# Microcontroller.net
KiCad netlist of a schematic drawn in Altium Designer
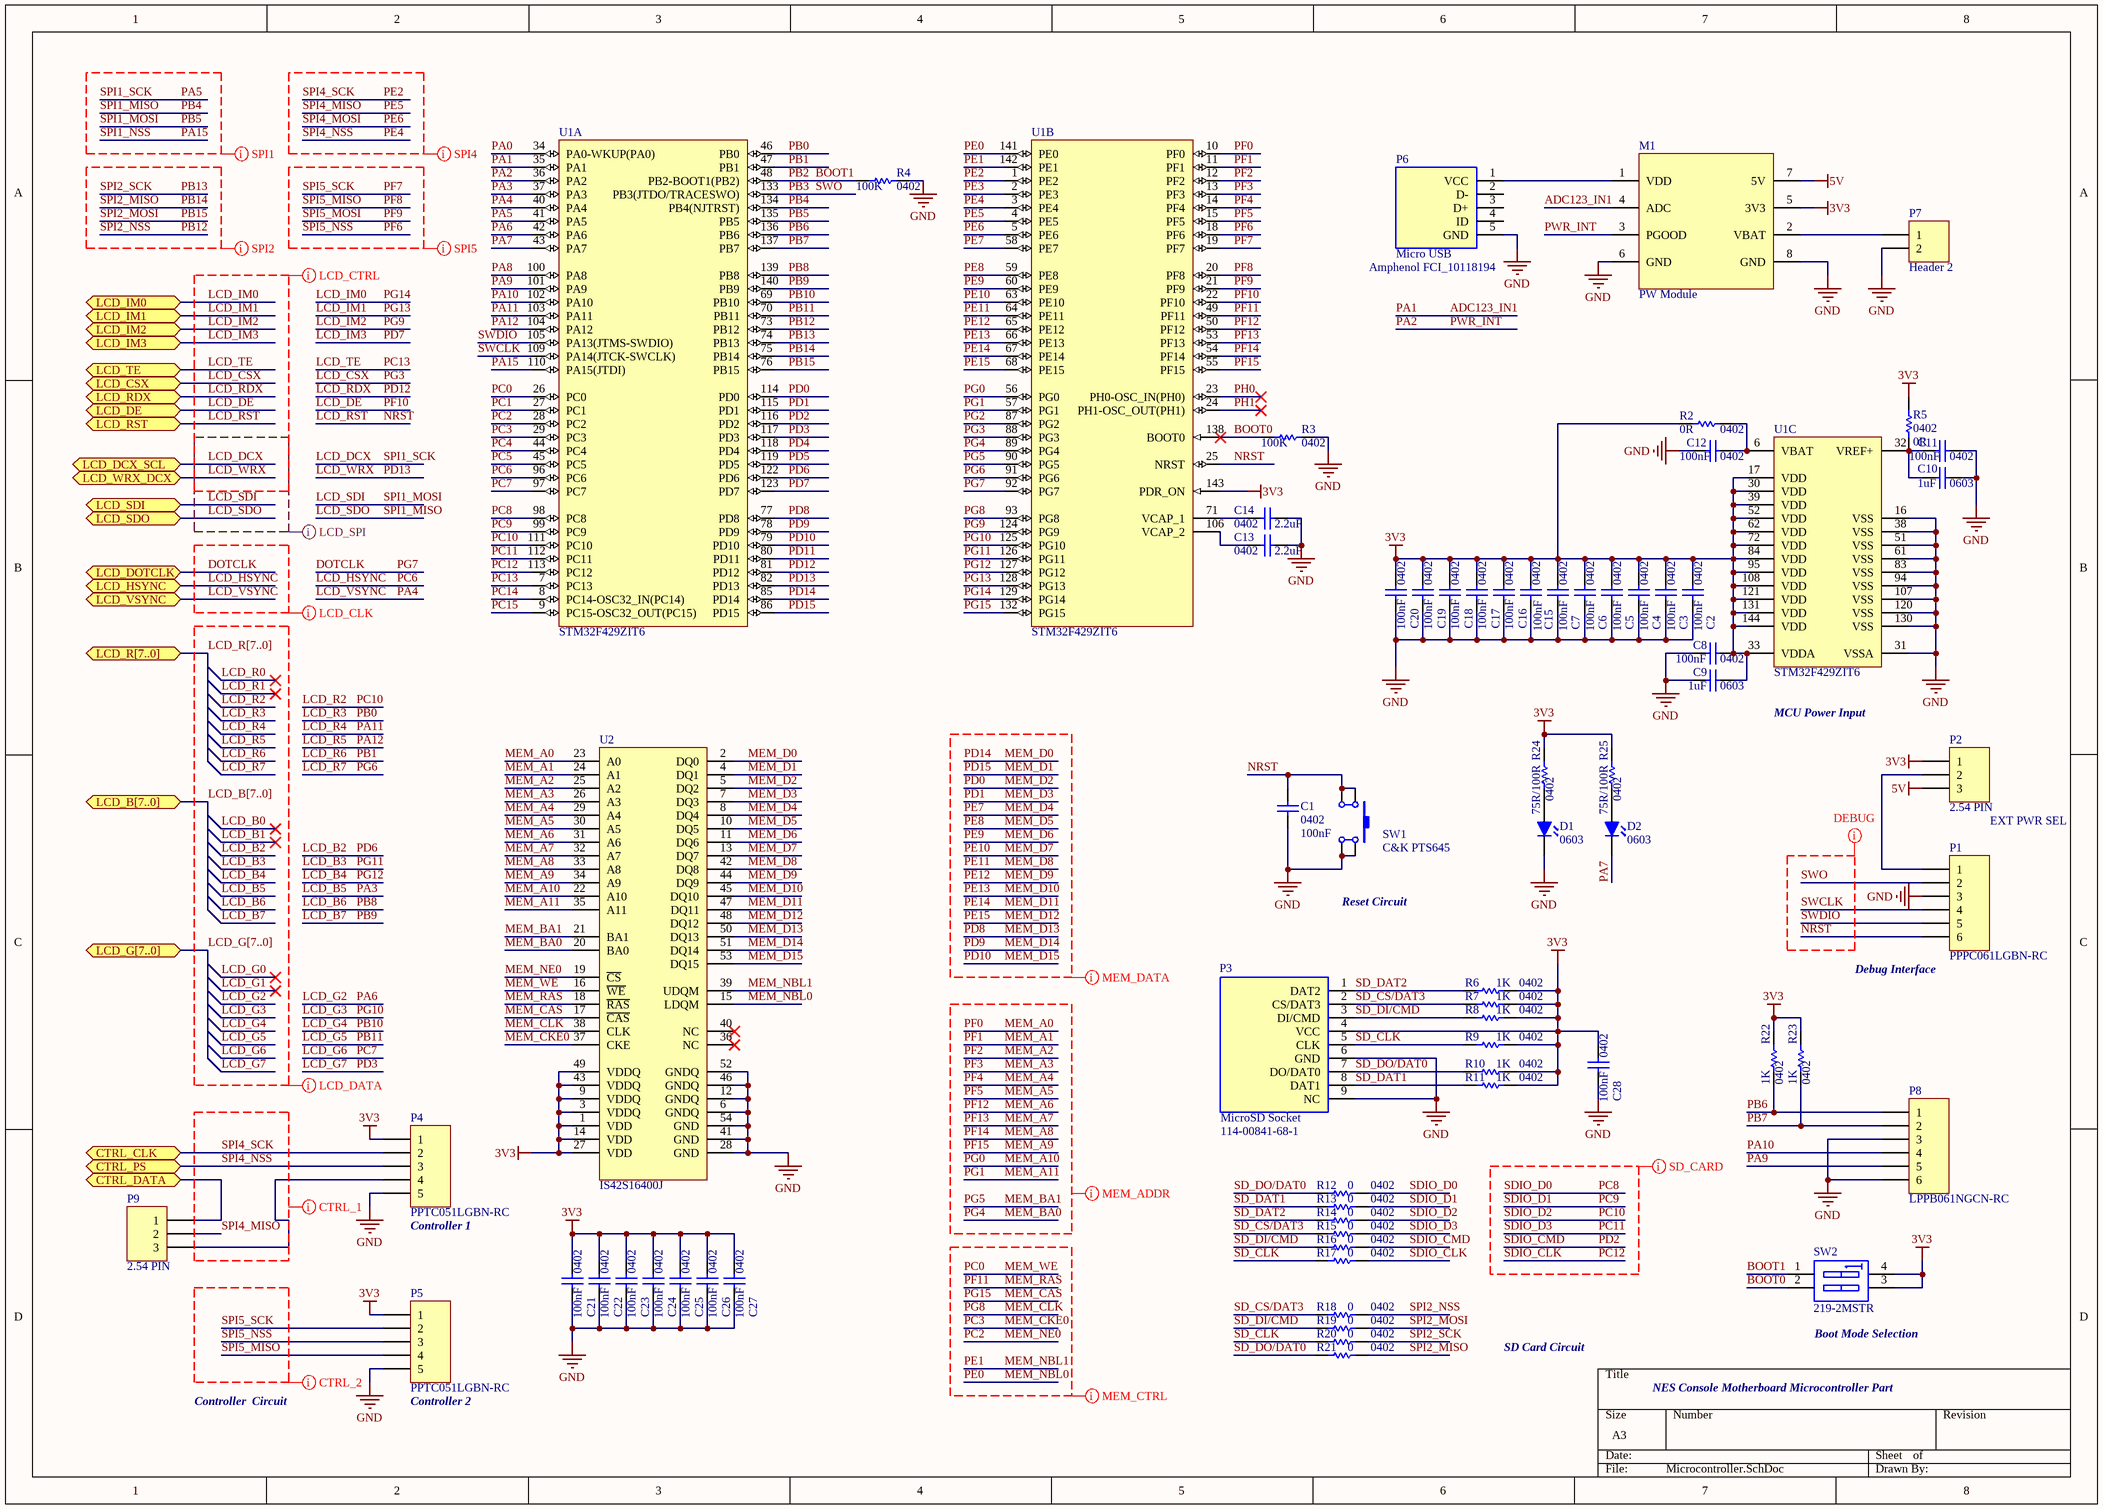
[diagram p0: Microcontroller.SchDoc]

(export (version "E")
  (design (tool "Eeschema 10.0.6"))
  (components
    (comp (ref "C1")
      (value "0402")
      (footprint "CAPC1005X07N")
      (description "Capacitor")
      (fields (field (name "ALTIUM_VALUE") "100nF") (field (name "PUBLISHER") "Altium Limited"))
      (libsource (lib "Miscellaneous Devices") (part "Cap"))
    )
    (comp (ref "C2")
      (value "0402")
      (footprint "CAPC1005X07N")
      (description "Capacitor")
      (fields (field (name "ALTIUM_VALUE") "100nF") (field (name "PUBLISHER") "Altium Limited"))
      (libsource (lib "Miscellaneous Devices") (part "Cap"))
    )
    (comp (ref "C3")
      (value "0402")
      (footprint "CAPC1005X07N")
      (description "Capacitor")
      (fields (field (name "ALTIUM_VALUE") "100nF") (field (name "PUBLISHER") "Altium Limited"))
      (libsource (lib "Miscellaneous Devices") (part "Cap"))
    )
    (comp (ref "C4")
      (value "0402")
      (footprint "CAPC1005X07N")
      (description "Capacitor")
      (fields (field (name "ALTIUM_VALUE") "100nF") (field (name "PUBLISHER") "Altium Limited"))
      (libsource (lib "Miscellaneous Devices") (part "Cap"))
    )
    (comp (ref "C5")
      (value "0402")
      (footprint "CAPC1005X07N")
      (description "Capacitor")
      (fields (field (name "ALTIUM_VALUE") "100nF") (field (name "PUBLISHER") "Altium Limited"))
      (libsource (lib "Miscellaneous Devices") (part "Cap"))
    )
    (comp (ref "C6")
      (value "0402")
      (footprint "CAPC1005X07N")
      (description "Capacitor")
      (fields (field (name "ALTIUM_VALUE") "100nF") (field (name "PUBLISHER") "Altium Limited"))
      (libsource (lib "Miscellaneous Devices") (part "Cap"))
    )
    (comp (ref "C7")
      (value "0402")
      (footprint "CAPC1005X07N")
      (description "Capacitor")
      (fields (field (name "ALTIUM_VALUE") "100nF") (field (name "PUBLISHER") "Altium Limited"))
      (libsource (lib "Miscellaneous Devices") (part "Cap"))
    )
    (comp (ref "C8")
      (value "0402")
      (footprint "CAPC1005X07N")
      (description "Capacitor")
      (fields (field (name "ALTIUM_VALUE") "100nF") (field (name "PUBLISHER") "Altium Limited"))
      (libsource (lib "Miscellaneous Devices") (part "Cap"))
    )
    (comp (ref "C9")
      (value "0603")
      (footprint "CAPC1608X10N")
      (description "Capacitor")
      (fields (field (name "ALTIUM_VALUE") "1uF") (field (name "PUBLISHER") "Altium Limited"))
      (libsource (lib "Miscellaneous Devices") (part "Cap"))
    )
    (comp (ref "C10")
      (value "0603")
      (footprint "CAPC1608X10N")
      (description "Capacitor")
      (fields (field (name "ALTIUM_VALUE") "1uF") (field (name "PUBLISHER") "Altium Limited"))
      (libsource (lib "Miscellaneous Devices") (part "Cap"))
    )
    (comp (ref "C11")
      (value "0402")
      (footprint "CAPC1005X07N")
      (description "Capacitor")
      (fields (field (name "ALTIUM_VALUE") "100nF") (field (name "PUBLISHER") "Altium Limited"))
      (libsource (lib "Miscellaneous Devices") (part "Cap"))
    )
    (comp (ref "C12")
      (value "0402")
      (footprint "CAPC1005X07N")
      (description "Capacitor")
      (fields (field (name "ALTIUM_VALUE") "100nF") (field (name "PUBLISHER") "Altium Limited"))
      (libsource (lib "Miscellaneous Devices") (part "Cap"))
    )
    (comp (ref "C13")
      (value "0402")
      (footprint "CAPC1005X07N")
      (description "Capacitor")
      (fields (field (name "ALTIUM_VALUE") "2.2uF") (field (name "PUBLISHER") "Altium Limited"))
      (libsource (lib "Miscellaneous Devices") (part "Cap"))
    )
    (comp (ref "C14")
      (value "0402")
      (footprint "CAPC1005X07N")
      (description "Capacitor")
      (fields (field (name "ALTIUM_VALUE") "2.2uF") (field (name "PUBLISHER") "Altium Limited"))
      (libsource (lib "Miscellaneous Devices") (part "Cap"))
    )
    (comp (ref "C15")
      (value "0402")
      (footprint "CAPC1005X07N")
      (description "Capacitor")
      (fields (field (name "ALTIUM_VALUE") "100nF") (field (name "PUBLISHER") "Altium Limited"))
      (libsource (lib "Miscellaneous Devices") (part "Cap"))
    )
    (comp (ref "C16")
      (value "0402")
      (footprint "CAPC1005X07N")
      (description "Capacitor")
      (fields (field (name "ALTIUM_VALUE") "100nF") (field (name "PUBLISHER") "Altium Limited"))
      (libsource (lib "Miscellaneous Devices") (part "Cap"))
    )
    (comp (ref "C17")
      (value "0402")
      (footprint "CAPC1005X07N")
      (description "Capacitor")
      (fields (field (name "ALTIUM_VALUE") "100nF") (field (name "PUBLISHER") "Altium Limited"))
      (libsource (lib "Miscellaneous Devices") (part "Cap"))
    )
    (comp (ref "C18")
      (value "0402")
      (footprint "CAPC1005X07N")
      (description "Capacitor")
      (fields (field (name "ALTIUM_VALUE") "100nF") (field (name "PUBLISHER") "Altium Limited"))
      (libsource (lib "Miscellaneous Devices") (part "Cap"))
    )
    (comp (ref "C19")
      (value "0402")
      (footprint "CAPC1005X07N")
      (description "Capacitor")
      (fields (field (name "ALTIUM_VALUE") "100nF") (field (name "PUBLISHER") "Altium Limited"))
      (libsource (lib "Miscellaneous Devices") (part "Cap"))
    )
    (comp (ref "C20")
      (value "0402")
      (footprint "CAPC1005X07N")
      (description "Capacitor")
      (fields (field (name "ALTIUM_VALUE") "100nF") (field (name "PUBLISHER") "Altium Limited"))
      (libsource (lib "Miscellaneous Devices") (part "Cap"))
    )
    (comp (ref "C21")
      (value "0402")
      (footprint "CAPC1005X07N")
      (description "Capacitor")
      (fields (field (name "ALTIUM_VALUE") "100nF") (field (name "PUBLISHER") "Altium Limited"))
      (libsource (lib "Miscellaneous Devices") (part "Cap"))
    )
    (comp (ref "C22")
      (value "0402")
      (footprint "CAPC1005X07N")
      (description "Capacitor")
      (fields (field (name "ALTIUM_VALUE") "100nF") (field (name "PUBLISHER") "Altium Limited"))
      (libsource (lib "Miscellaneous Devices") (part "Cap"))
    )
    (comp (ref "C23")
      (value "0402")
      (footprint "CAPC1005X07N")
      (description "Capacitor")
      (fields (field (name "ALTIUM_VALUE") "100nF") (field (name "PUBLISHER") "Altium Limited"))
      (libsource (lib "Miscellaneous Devices") (part "Cap"))
    )
    (comp (ref "C24")
      (value "0402")
      (footprint "CAPC1005X07N")
      (description "Capacitor")
      (fields (field (name "ALTIUM_VALUE") "100nF") (field (name "PUBLISHER") "Altium Limited"))
      (libsource (lib "Miscellaneous Devices") (part "Cap"))
    )
    (comp (ref "C25")
      (value "0402")
      (footprint "CAPC1005X07N")
      (description "Capacitor")
      (fields (field (name "ALTIUM_VALUE") "100nF") (field (name "PUBLISHER") "Altium Limited"))
      (libsource (lib "Miscellaneous Devices") (part "Cap"))
    )
    (comp (ref "C26")
      (value "0402")
      (footprint "CAPC1005X07N")
      (description "Capacitor")
      (fields (field (name "ALTIUM_VALUE") "100nF") (field (name "PUBLISHER") "Altium Limited"))
      (libsource (lib "Miscellaneous Devices") (part "Cap"))
    )
    (comp (ref "C27")
      (value "0402")
      (footprint "CAPC1005X07N")
      (description "Capacitor")
      (fields (field (name "ALTIUM_VALUE") "100nF") (field (name "PUBLISHER") "Altium Limited"))
      (libsource (lib "Miscellaneous Devices") (part "Cap"))
    )
    (comp (ref "C28")
      (value "0402")
      (footprint "CAPC1005X07N")
      (description "Capacitor")
      (fields (field (name "ALTIUM_VALUE") "100nF") (field (name "PUBLISHER") "Altium Limited"))
      (libsource (lib "Miscellaneous Devices") (part "Cap"))
    )
    (comp (ref "D1")
      (value "0603")
      (footprint "RESC1608X06N")
      (description "General LED")
      (libsource (lib "Schematic_Diode") (part "LED-1"))
    )
    (comp (ref "D2")
      (value "0603")
      (footprint "RESC1608X06N")
      (description "General LED")
      (libsource (lib "Schematic_Diode") (part "LED-1"))
    )
    (comp (ref "M1")
      (value "PW Module")
      (footprint "Power Module")
      (description "Power Supply Module")
      (libsource (lib "Schematic_Modules_NES") (part "PW Module"))
    )
    (comp (ref "P1")
      (value "PPPC061LGBN-RC")
      (footprint "HDR1X6_RANG")
      (description "Header, 6-Pin")
      (fields (field (name "PUBLISHER") "Altium Limited"))
      (libsource (lib "Miscellaneous Connectors") (part "Header 6"))
    )
    (comp (ref "P2")
      (value "2.54 PIN")
      (footprint "HDR1X3")
      (description "Header, 3-Pin")
      (fields (field (name "PUBLISHER") "Altium Limited"))
      (libsource (lib "Miscellaneous Connectors") (part "Header 3"))
    )
    (comp (ref "P3")
      (value "114-00841-68-1")
      (footprint "Amphenol_114-00841-68")
      (description "CONN MICRO SD CARD PUSH-PULL R/A")
      (fields
        (field (name "MANUFACTURER") "Amphenol Commercial")
        (field (name "MANUFACTURER PART NUMBER") "114-00841-68")
        (field (name "CONNECTOR TYPE") "MicroSD Socket")
      )
      (libsource (lib "Schematic_Connectors_USB") (part "Amphenol 114-00841-68-1"))
    )
    (comp (ref "P4")
      (value "PPTC051LGBN-RC")
      (footprint "HDR1X5_RANG")
      (description "Header, 5-Pin")
      (fields (field (name "PUBLISHER") "Altium Limited"))
      (libsource (lib "Miscellaneous Connectors") (part "Header 5"))
    )
    (comp (ref "P5")
      (value "PPTC051LGBN-RC")
      (footprint "HDR1X5_RANG")
      (description "Header, 5-Pin")
      (fields (field (name "PUBLISHER") "Altium Limited"))
      (libsource (lib "Miscellaneous Connectors") (part "Header 5"))
    )
    (comp (ref "P6")
      (value "Amphenol FCI_10118194")
      (footprint "USB_Mirco_Amphenol FCI_10118194")
      (description "General  Micro USB")
      (fields (field (name "CONNECTOR TYPE") "Micro USB"))
      (libsource (lib "Schematic_Connectors_USB") (part "CONN_MICRO_USB"))
    )
    (comp (ref "P7")
      (value "Header 2")
      (footprint "HDR1X2")
      (description "Header, 2-Pin")
      (fields (field (name "PUBLISHER") "Altium Limited"))
      (libsource (lib "Miscellaneous Connectors") (part "Header 2"))
    )
    (comp (ref "P8")
      (value "LPPB061NGCN-RC")
      (footprint "MHDR1X6_RANG")
      (description "Header, 6-Pin")
      (fields (field (name "PUBLISHER") "Altium Limited"))
      (libsource (lib "Miscellaneous Connectors") (part "Header 6"))
    )
    (comp (ref "P9")
      (value "2.54 PIN")
      (footprint "HDR1X3")
      (description "Header, 3-Pin")
      (fields (field (name "PUBLISHER") "Altium Limited"))
      (libsource (lib "") (part "Header 3_1"))
    )
    (comp (ref "R2")
      (value "0402")
      (footprint "RESC1005X04N")
      (description "Resistor")
      (fields (field (name "ALTIUM_VALUE") "0R") (field (name "PUBLISHER") "Altium Limited"))
      (libsource (lib "Miscellaneous Devices") (part "Res1"))
    )
    (comp (ref "R3")
      (value "0402")
      (footprint "RESC1005X04N")
      (description "Resistor")
      (fields (field (name "ALTIUM_VALUE") "100K") (field (name "PUBLISHER") "Altium Limited"))
      (libsource (lib "Miscellaneous Devices") (part "Res1"))
    )
    (comp (ref "R4")
      (value "0402")
      (footprint "RESC1005X04N")
      (description "Resistor")
      (fields (field (name "ALTIUM_VALUE") "100K") (field (name "PUBLISHER") "Altium Limited"))
      (libsource (lib "Miscellaneous Devices") (part "Res1"))
    )
    (comp (ref "R5")
      (value "0402")
      (footprint "RESC1005X04N")
      (description "Resistor")
      (fields (field (name "ALTIUM_VALUE") "0R") (field (name "PUBLISHER") "Altium Limited"))
      (libsource (lib "Miscellaneous Devices") (part "Res1"))
    )
    (comp (ref "R6")
      (value "0402")
      (footprint "RESC1005X04N")
      (description "Resistor")
      (fields (field (name "ALTIUM_VALUE") "1K") (field (name "PUBLISHER") "Altium Limited"))
      (libsource (lib "Miscellaneous Devices") (part "Res1"))
    )
    (comp (ref "R7")
      (value "0402")
      (footprint "RESC1005X04N")
      (description "Resistor")
      (fields (field (name "ALTIUM_VALUE") "1K") (field (name "PUBLISHER") "Altium Limited"))
      (libsource (lib "Miscellaneous Devices") (part "Res1"))
    )
    (comp (ref "R8")
      (value "0402")
      (footprint "RESC1005X04N")
      (description "Resistor")
      (fields (field (name "ALTIUM_VALUE") "1K") (field (name "PUBLISHER") "Altium Limited"))
      (libsource (lib "Miscellaneous Devices") (part "Res1"))
    )
    (comp (ref "R9")
      (value "0402")
      (footprint "RESC1005X04N")
      (description "Resistor")
      (fields (field (name "ALTIUM_VALUE") "1K") (field (name "PUBLISHER") "Altium Limited"))
      (libsource (lib "Miscellaneous Devices") (part "Res1"))
    )
    (comp (ref "R10")
      (value "0402")
      (footprint "RESC1005X04N")
      (description "Resistor")
      (fields (field (name "ALTIUM_VALUE") "1K") (field (name "PUBLISHER") "Altium Limited"))
      (libsource (lib "Miscellaneous Devices") (part "Res1"))
    )
    (comp (ref "R11")
      (value "0402")
      (footprint "RESC1005X04N")
      (description "Resistor")
      (fields (field (name "ALTIUM_VALUE") "1K") (field (name "PUBLISHER") "Altium Limited"))
      (libsource (lib "Miscellaneous Devices") (part "Res1"))
    )
    (comp (ref "R12")
      (value "0402")
      (footprint "RESC1005X04N")
      (description "Resistor")
      (fields (field (name "ALTIUM_VALUE") "0") (field (name "PUBLISHER") "Altium Limited"))
      (libsource (lib "Miscellaneous Devices") (part "Res1"))
    )
    (comp (ref "R13")
      (value "0402")
      (footprint "RESC1005X04N")
      (description "Resistor")
      (fields (field (name "ALTIUM_VALUE") "0") (field (name "PUBLISHER") "Altium Limited"))
      (libsource (lib "Miscellaneous Devices") (part "Res1"))
    )
    (comp (ref "R14")
      (value "0402")
      (footprint "RESC1005X04N")
      (description "Resistor")
      (fields (field (name "ALTIUM_VALUE") "0") (field (name "PUBLISHER") "Altium Limited"))
      (libsource (lib "Miscellaneous Devices") (part "Res1"))
    )
    (comp (ref "R15")
      (value "0402")
      (footprint "RESC1005X04N")
      (description "Resistor")
      (fields (field (name "ALTIUM_VALUE") "0") (field (name "PUBLISHER") "Altium Limited"))
      (libsource (lib "Miscellaneous Devices") (part "Res1"))
    )
    (comp (ref "R16")
      (value "0402")
      (footprint "RESC1005X04N")
      (description "Resistor")
      (fields (field (name "ALTIUM_VALUE") "0") (field (name "PUBLISHER") "Altium Limited"))
      (libsource (lib "Miscellaneous Devices") (part "Res1"))
    )
    (comp (ref "R17")
      (value "0402")
      (footprint "RESC1005X04N")
      (description "Resistor")
      (fields (field (name "ALTIUM_VALUE") "0") (field (name "PUBLISHER") "Altium Limited"))
      (libsource (lib "Miscellaneous Devices") (part "Res1"))
    )
    (comp (ref "R18")
      (value "0402")
      (footprint "RESC1005X04N")
      (description "Resistor")
      (fields (field (name "ALTIUM_VALUE") "0") (field (name "PUBLISHER") "Altium Limited"))
      (libsource (lib "Miscellaneous Devices") (part "Res1"))
    )
    (comp (ref "R19")
      (value "0402")
      (footprint "RESC1005X04N")
      (description "Resistor")
      (fields (field (name "ALTIUM_VALUE") "0") (field (name "PUBLISHER") "Altium Limited"))
      (libsource (lib "Miscellaneous Devices") (part "Res1"))
    )
    (comp (ref "R20")
      (value "0402")
      (footprint "RESC1005X04N")
      (description "Resistor")
      (fields (field (name "ALTIUM_VALUE") "0") (field (name "PUBLISHER") "Altium Limited"))
      (libsource (lib "Miscellaneous Devices") (part "Res1"))
    )
    (comp (ref "R21")
      (value "0402")
      (footprint "RESC1005X04N")
      (description "Resistor")
      (fields (field (name "ALTIUM_VALUE") "0") (field (name "PUBLISHER") "Altium Limited"))
      (libsource (lib "Miscellaneous Devices") (part "Res1"))
    )
    (comp (ref "R22")
      (value "0402")
      (footprint "RESC1005X04N")
      (description "Resistor")
      (fields (field (name "ALTIUM_VALUE") "1K") (field (name "PUBLISHER") "Altium Limited"))
      (libsource (lib "Miscellaneous Devices") (part "Res1"))
    )
    (comp (ref "R23")
      (value "0402")
      (footprint "RESC1005X04N")
      (description "Resistor")
      (fields (field (name "ALTIUM_VALUE") "1K") (field (name "PUBLISHER") "Altium Limited"))
      (libsource (lib "Miscellaneous Devices") (part "Res1"))
    )
    (comp (ref "R24")
      (value "0402")
      (footprint "RESC1005X04N")
      (description "Resistor")
      (fields (field (name "ALTIUM_VALUE") "75R/100R") (field (name "PUBLISHER") "Altium Limited"))
      (libsource (lib "Miscellaneous Devices") (part "Res1"))
    )
    (comp (ref "R25")
      (value "0402")
      (footprint "RESC1005X04N")
      (description "Resistor")
      (fields (field (name "ALTIUM_VALUE") "75R/100R") (field (name "PUBLISHER") "Altium Limited"))
      (libsource (lib "Miscellaneous Devices") (part "Res1"))
    )
    (comp (ref "SW1")
      (value "C&K PTS645")
      (footprint "C&K_PTS645_SMT")
      (description "General Tactile Switch")
      (libsource (lib "Schematic_Switches") (part "SW_TACT"))
    )
    (comp (ref "SW2")
      (value "219-2MSTR")
      (footprint "CTS_219-2_SMT")
      (description "DIP Switch, 2 Position, SPST")
      (fields (field (name "PUBLISHER") "Altium Limited"))
      (libsource (lib "Schematic_Switches") (part "SW_DIP-2"))
    )
    (comp (ref "U1")
      (value "STM32F429ZIT6")
      (footprint "STM-LQFP144_N")
      (fields (field (name "MANUFACTURER") "STMicroelectronics"))
      (libsource (lib "STMicroelectronics STM32 F4") (part "STM32F429ZIT6"))
    )
    (comp (ref "U2")
      (value "IS42S16400J")
      (footprint "TSOP80P1180X120-54N")
      (description "DRAM 64M (4Mx16) 166MHz SDR SDRAM, 3.3V")
      (fields
        (field (name "MANUFACTURER") "ISSI")
        (field (name "MANUFACTURER PART NUMBER") "IS42S16400J-6TLI")
      )
      (libsource (lib "Schematic_Memory") (part "IS42S16400J"))
    )
  )
  (nets
    (net (code "1") (name "/ADC123_IN1") (class "Default")
      (node (ref "M1") (pin "4") (pinfunction "ADC_4") (pintype "passive"))
      (node (ref "U1") (pin "35") (pinfunction "PA1_35") (pintype "bidirectional"))
    )
    (net (code "2") (name "/BOOT0") (class "Default")
      (node (ref "R3") (pin "2") (pinfunction "2_2") (pintype "passive"))
      (node (ref "SW2") (pin "2") (pinfunction "A2_2") (pintype "passive"))
      (node (ref "U1") (pin "138") (pinfunction "BOOT0_138") (pintype "input"))
    )
    (net (code "3") (name "/BOOT1") (class "Default")
      (node (ref "R4") (pin "2") (pinfunction "2_2") (pintype "passive"))
      (node (ref "SW2") (pin "1") (pinfunction "A1_1") (pintype "passive"))
      (node (ref "U1") (pin "48") (pinfunction "PB2-BOOT1(PB2)_48") (pintype "bidirectional"))
    )
    (net (code "4") (name "/CTRL_DATA") (class "Default")
      (node (ref "P9") (pin "1") (pinfunction "1_1") (pintype "passive"))
    )
    (net (code "5") (name "/DOTCLK") (class "Default")
      (node (ref "U1") (pin "92") (pinfunction "PG7_92") (pintype "bidirectional"))
    )
    (net (code "8") (name "/LCD_B2") (class "Default")
      (node (ref "U1") (pin "122") (pinfunction "PD6_122") (pintype "bidirectional"))
    )
    (net (code "9") (name "/LCD_B3") (class "Default")
      (node (ref "U1") (pin "126") (pinfunction "PG11_126") (pintype "bidirectional"))
    )
    (net (code "10") (name "/LCD_B4") (class "Default")
      (node (ref "U1") (pin "127") (pinfunction "PG12_127") (pintype "bidirectional"))
    )
    (net (code "11") (name "/LCD_B5") (class "Default")
      (node (ref "U1") (pin "37") (pinfunction "PA3_37") (pintype "bidirectional"))
    )
    (net (code "12") (name "/LCD_B6") (class "Default")
      (node (ref "U1") (pin "139") (pinfunction "PB8_139") (pintype "bidirectional"))
    )
    (net (code "13") (name "/LCD_B7") (class "Default")
      (node (ref "U1") (pin "140") (pinfunction "PB9_140") (pintype "bidirectional"))
    )
    (net (code "15") (name "/LCD_CSX") (class "Default")
      (node (ref "U1") (pin "88") (pinfunction "PG3_88") (pintype "bidirectional"))
    )
    (net (code "16") (name "/LCD_DCX") (class "Default")
      (node (ref "U1") (pin "41") (pinfunction "PA5_41") (pintype "bidirectional"))
    )
    (net (code "17") (name "/LCD_DE") (class "Default")
      (node (ref "U1") (pin "22") (pinfunction "PF10_22") (pintype "bidirectional"))
    )
    (net (code "20") (name "/LCD_G2") (class "Default")
      (node (ref "U1") (pin "42") (pinfunction "PA6_42") (pintype "bidirectional"))
    )
    (net (code "21") (name "/LCD_G3") (class "Default")
      (node (ref "U1") (pin "125") (pinfunction "PG10_125") (pintype "bidirectional"))
    )
    (net (code "22") (name "/LCD_G4") (class "Default")
      (node (ref "U1") (pin "69") (pinfunction "PB10_69") (pintype "bidirectional"))
    )
    (net (code "23") (name "/LCD_G5") (class "Default")
      (node (ref "U1") (pin "70") (pinfunction "PB11_70") (pintype "bidirectional"))
    )
    (net (code "24") (name "/LCD_G6") (class "Default")
      (node (ref "U1") (pin "97") (pinfunction "PC7_97") (pintype "bidirectional"))
    )
    (net (code "25") (name "/LCD_G7") (class "Default")
      (node (ref "U1") (pin "117") (pinfunction "PD3_117") (pintype "bidirectional"))
    )
    (net (code "27") (name "/LCD_HSYNC") (class "Default")
      (node (ref "U1") (pin "96") (pinfunction "PC6_96") (pintype "bidirectional"))
    )
    (net (code "28") (name "/LCD_IM0") (class "Default")
      (node (ref "U1") (pin "129") (pinfunction "PG14_129") (pintype "bidirectional"))
    )
    (net (code "29") (name "/LCD_IM1") (class "Default")
      (node (ref "U1") (pin "128") (pinfunction "PG13_128") (pintype "bidirectional"))
    )
    (net (code "30") (name "/LCD_IM2") (class "Default")
      (node (ref "U1") (pin "124") (pinfunction "PG9_124") (pintype "bidirectional"))
    )
    (net (code "31") (name "/LCD_IM3") (class "Default")
      (node (ref "U1") (pin "123") (pinfunction "PD7_123") (pintype "bidirectional"))
    )
    (net (code "34") (name "/LCD_R2") (class "Default")
      (node (ref "R14") (pin "1") (pinfunction "1_1") (pintype "passive"))
      (node (ref "U1") (pin "111") (pinfunction "PC10_111") (pintype "bidirectional"))
    )
    (net (code "35") (name "/LCD_R3") (class "Default")
      (node (ref "U1") (pin "46") (pinfunction "PB0_46") (pintype "bidirectional"))
    )
    (net (code "36") (name "/LCD_R4") (class "Default")
      (node (ref "U1") (pin "103") (pinfunction "PA11_103") (pintype "bidirectional"))
    )
    (net (code "37") (name "/LCD_R5") (class "Default")
      (node (ref "U1") (pin "104") (pinfunction "PA12_104") (pintype "bidirectional"))
    )
    (net (code "38") (name "/LCD_R6") (class "Default")
      (node (ref "U1") (pin "47") (pinfunction "PB1_47") (pintype "bidirectional"))
    )
    (net (code "39") (name "/LCD_R7") (class "Default")
      (node (ref "U1") (pin "91") (pinfunction "PG6_91") (pintype "bidirectional"))
    )
    (net (code "40") (name "/LCD_RDX") (class "Default")
      (node (ref "U1") (pin "81") (pinfunction "PD12_81") (pintype "bidirectional"))
    )
    (net (code "41") (name "/LCD_RST") (class "Default")
      (node (ref "C1") (pin "2") (pinfunction "2_2") (pintype "passive"))
      (node (ref "P1") (pin "6") (pinfunction "6_6") (pintype "passive"))
      (node (ref "SW1") (pin "1") (pinfunction "1_1") (pintype "passive"))
      (node (ref "SW1") (pin "2") (pinfunction "2_2") (pintype "passive"))
      (node (ref "U1") (pin "25") (pinfunction "NRST_25") (pintype "bidirectional"))
    )
    (net (code "43") (name "/LCD_SDI") (class "Default")
      (node (ref "U1") (pin "135") (pinfunction "PB5_135") (pintype "bidirectional"))
    )
    (net (code "44") (name "/LCD_SDO") (class "Default")
      (node (ref "U1") (pin "134") (pinfunction "PB4(NJTRST)_134") (pintype "bidirectional"))
    )
    (net (code "45") (name "/LCD_TE") (class "Default")
      (node (ref "U1") (pin "7") (pinfunction "PC13_7") (pintype "bidirectional"))
    )
    (net (code "46") (name "/LCD_VSYNC") (class "Default")
      (node (ref "U1") (pin "40") (pinfunction "PA4_40") (pintype "bidirectional"))
    )
    (net (code "47") (name "/LCD_WRX") (class "Default")
      (node (ref "U1") (pin "82") (pinfunction "PD13_82") (pintype "bidirectional"))
    )
    (net (code "48") (name "/MEM_A0") (class "Default")
      (node (ref "U1") (pin "10") (pinfunction "PF0_10") (pintype "bidirectional"))
      (node (ref "U2") (pin "23") (pinfunction "A0_23") (pintype "passive"))
    )
    (net (code "49") (name "/MEM_A1") (class "Default")
      (node (ref "U1") (pin "11") (pinfunction "PF1_11") (pintype "bidirectional"))
      (node (ref "U2") (pin "24") (pinfunction "A1_24") (pintype "passive"))
    )
    (net (code "50") (name "/MEM_A2") (class "Default")
      (node (ref "U1") (pin "12") (pinfunction "PF2_12") (pintype "bidirectional"))
      (node (ref "U2") (pin "25") (pinfunction "A2_25") (pintype "passive"))
    )
    (net (code "51") (name "/MEM_A3") (class "Default")
      (node (ref "U1") (pin "13") (pinfunction "PF3_13") (pintype "bidirectional"))
      (node (ref "U2") (pin "26") (pinfunction "A3_26") (pintype "passive"))
    )
    (net (code "52") (name "/MEM_A4") (class "Default")
      (node (ref "U1") (pin "14") (pinfunction "PF4_14") (pintype "bidirectional"))
      (node (ref "U2") (pin "29") (pinfunction "A4_29") (pintype "passive"))
    )
    (net (code "53") (name "/MEM_A5") (class "Default")
      (node (ref "U1") (pin "15") (pinfunction "PF5_15") (pintype "bidirectional"))
      (node (ref "U2") (pin "30") (pinfunction "A5_30") (pintype "passive"))
    )
    (net (code "54") (name "/MEM_A6") (class "Default")
      (node (ref "U1") (pin "50") (pinfunction "PF12_50") (pintype "bidirectional"))
      (node (ref "U2") (pin "31") (pinfunction "A6_31") (pintype "passive"))
    )
    (net (code "55") (name "/MEM_A7") (class "Default")
      (node (ref "U1") (pin "53") (pinfunction "PF13_53") (pintype "bidirectional"))
      (node (ref "U2") (pin "32") (pinfunction "A7_32") (pintype "passive"))
    )
    (net (code "56") (name "/MEM_A8") (class "Default")
      (node (ref "U1") (pin "54") (pinfunction "PF14_54") (pintype "bidirectional"))
      (node (ref "U2") (pin "33") (pinfunction "A8_33") (pintype "passive"))
    )
    (net (code "57") (name "/MEM_A9") (class "Default")
      (node (ref "U1") (pin "55") (pinfunction "PF15_55") (pintype "bidirectional"))
      (node (ref "U2") (pin "34") (pinfunction "A9_34") (pintype "passive"))
    )
    (net (code "58") (name "/MEM_A10") (class "Default")
      (node (ref "U1") (pin "56") (pinfunction "PG0_56") (pintype "bidirectional"))
      (node (ref "U2") (pin "22") (pinfunction "A10_22") (pintype "passive"))
    )
    (net (code "59") (name "/MEM_A11") (class "Default")
      (node (ref "U1") (pin "57") (pinfunction "PG1_57") (pintype "bidirectional"))
      (node (ref "U2") (pin "35") (pinfunction "A11_35") (pintype "passive"))
    )
    (net (code "60") (name "/MEM_BA0") (class "Default")
      (node (ref "U1") (pin "89") (pinfunction "PG4_89") (pintype "bidirectional"))
      (node (ref "U2") (pin "20") (pinfunction "BA0_20") (pintype "passive"))
    )
    (net (code "61") (name "/MEM_BA1") (class "Default")
      (node (ref "U1") (pin "90") (pinfunction "PG5_90") (pintype "bidirectional"))
      (node (ref "U2") (pin "21") (pinfunction "BA1_21") (pintype "passive"))
    )
    (net (code "62") (name "/MEM_CAS") (class "Default")
      (node (ref "U1") (pin "132") (pinfunction "PG15_132") (pintype "bidirectional"))
      (node (ref "U2") (pin "17") (pinfunction "~{CAS}_17") (pintype "passive"))
    )
    (net (code "63") (name "/MEM_CKE0") (class "Default")
      (node (ref "U1") (pin "29") (pinfunction "PC3_29") (pintype "bidirectional"))
      (node (ref "U2") (pin "37") (pinfunction "CKE_37") (pintype "passive"))
    )
    (net (code "64") (name "/MEM_CLK") (class "Default")
      (node (ref "U1") (pin "93") (pinfunction "PG8_93") (pintype "bidirectional"))
      (node (ref "U2") (pin "38") (pinfunction "CLK_38") (pintype "passive"))
    )
    (net (code "65") (name "/MEM_D0") (class "Default")
      (node (ref "U1") (pin "85") (pinfunction "PD14_85") (pintype "bidirectional"))
      (node (ref "U2") (pin "2") (pinfunction "DQ0_2") (pintype "passive"))
    )
    (net (code "66") (name "/MEM_D1") (class "Default")
      (node (ref "U1") (pin "86") (pinfunction "PD15_86") (pintype "bidirectional"))
      (node (ref "U2") (pin "4") (pinfunction "DQ1_4") (pintype "passive"))
    )
    (net (code "67") (name "/MEM_D2") (class "Default")
      (node (ref "U1") (pin "114") (pinfunction "PD0_114") (pintype "bidirectional"))
      (node (ref "U2") (pin "5") (pinfunction "DQ2_5") (pintype "passive"))
    )
    (net (code "68") (name "/MEM_D3") (class "Default")
      (node (ref "U1") (pin "115") (pinfunction "PD1_115") (pintype "bidirectional"))
      (node (ref "U2") (pin "7") (pinfunction "DQ3_7") (pintype "passive"))
    )
    (net (code "69") (name "/MEM_D4") (class "Default")
      (node (ref "U1") (pin "58") (pinfunction "PE7_58") (pintype "bidirectional"))
      (node (ref "U2") (pin "8") (pinfunction "DQ4_8") (pintype "passive"))
    )
    (net (code "70") (name "/MEM_D5") (class "Default")
      (node (ref "U1") (pin "59") (pinfunction "PE8_59") (pintype "bidirectional"))
      (node (ref "U2") (pin "10") (pinfunction "DQ5_10") (pintype "passive"))
    )
    (net (code "71") (name "/MEM_D6") (class "Default")
      (node (ref "U1") (pin "60") (pinfunction "PE9_60") (pintype "bidirectional"))
      (node (ref "U2") (pin "11") (pinfunction "DQ6_11") (pintype "passive"))
    )
    (net (code "72") (name "/MEM_D7") (class "Default")
      (node (ref "U1") (pin "63") (pinfunction "PE10_63") (pintype "bidirectional"))
      (node (ref "U2") (pin "13") (pinfunction "DQ7_13") (pintype "passive"))
    )
    (net (code "73") (name "/MEM_D8") (class "Default")
      (node (ref "U1") (pin "64") (pinfunction "PE11_64") (pintype "bidirectional"))
      (node (ref "U2") (pin "42") (pinfunction "DQ8_42") (pintype "passive"))
    )
    (net (code "74") (name "/MEM_D9") (class "Default")
      (node (ref "U1") (pin "65") (pinfunction "PE12_65") (pintype "bidirectional"))
      (node (ref "U2") (pin "44") (pinfunction "DQ9_44") (pintype "passive"))
    )
    (net (code "75") (name "/MEM_D10") (class "Default")
      (node (ref "U1") (pin "66") (pinfunction "PE13_66") (pintype "bidirectional"))
      (node (ref "U2") (pin "45") (pinfunction "DQ10_45") (pintype "passive"))
    )
    (net (code "76") (name "/MEM_D11") (class "Default")
      (node (ref "U1") (pin "67") (pinfunction "PE14_67") (pintype "bidirectional"))
      (node (ref "U2") (pin "47") (pinfunction "DQ11_47") (pintype "passive"))
    )
    (net (code "77") (name "/MEM_D12") (class "Default")
      (node (ref "U1") (pin "68") (pinfunction "PE15_68") (pintype "bidirectional"))
      (node (ref "U2") (pin "48") (pinfunction "DQ12_48") (pintype "passive"))
    )
    (net (code "78") (name "/MEM_D13") (class "Default")
      (node (ref "U1") (pin "77") (pinfunction "PD8_77") (pintype "bidirectional"))
      (node (ref "U2") (pin "50") (pinfunction "DQ13_50") (pintype "passive"))
    )
    (net (code "79") (name "/MEM_D14") (class "Default")
      (node (ref "U1") (pin "78") (pinfunction "PD9_78") (pintype "bidirectional"))
      (node (ref "U2") (pin "51") (pinfunction "DQ14_51") (pintype "passive"))
    )
    (net (code "80") (name "/MEM_D15") (class "Default")
      (node (ref "U1") (pin "79") (pinfunction "PD10_79") (pintype "bidirectional"))
      (node (ref "U2") (pin "53") (pinfunction "DQ15_53") (pintype "passive"))
    )
    (net (code "81") (name "/MEM_NBL0") (class "Default")
      (node (ref "U1") (pin "141") (pinfunction "PE0_141") (pintype "bidirectional"))
      (node (ref "U2") (pin "15") (pinfunction "LDQM_15") (pintype "passive"))
    )
    (net (code "82") (name "/MEM_NBL1") (class "Default")
      (node (ref "U1") (pin "142") (pinfunction "PE1_142") (pintype "bidirectional"))
      (node (ref "U2") (pin "39") (pinfunction "UDQM_39") (pintype "passive"))
    )
    (net (code "83") (name "/MEM_NE0") (class "Default")
      (node (ref "U1") (pin "28") (pinfunction "PC2_28") (pintype "bidirectional"))
      (node (ref "U2") (pin "19") (pinfunction "~{CS}_19") (pintype "passive"))
    )
    (net (code "84") (name "/MEM_RAS") (class "Default")
      (node (ref "U1") (pin "49") (pinfunction "PF11_49") (pintype "bidirectional"))
      (node (ref "U2") (pin "18") (pinfunction "~{RAS}_18") (pintype "passive"))
    )
    (net (code "85") (name "/MEM_WE") (class "Default")
      (node (ref "U1") (pin "26") (pinfunction "PC0_26") (pintype "bidirectional"))
      (node (ref "U2") (pin "16") (pinfunction "~{WE}_16") (pintype "passive"))
    )
    (net (code "86") (name "/PA0") (class "Default")
      (node (ref "U1") (pin "34") (pinfunction "PA0-WKUP(PA0)_34") (pintype "bidirectional"))
    )
    (net (code "87") (name "/PA2") (class "Default")
      (node (ref "M1") (pin "3") (pinfunction "PGOOD_3") (pintype "passive"))
      (node (ref "U1") (pin "36") (pinfunction "PA2_36") (pintype "bidirectional"))
    )
    (net (code "88") (name "/PA7") (class "Default")
      (node (ref "D2") (pin "2") (pinfunction "-_2") (pintype "passive"))
      (node (ref "U1") (pin "43") (pinfunction "PA7_43") (pintype "bidirectional"))
    )
    (net (code "89") (name "/PA8") (class "Default")
      (node (ref "U1") (pin "100") (pinfunction "PA8_100") (pintype "bidirectional"))
    )
    (net (code "90") (name "/PA9") (class "Default")
      (node (ref "P8") (pin "5") (pinfunction "5_5") (pintype "passive"))
      (node (ref "U1") (pin "101") (pinfunction "PA9_101") (pintype "bidirectional"))
    )
    (net (code "91") (name "/PA10") (class "Default")
      (node (ref "P8") (pin "4") (pinfunction "4_4") (pintype "passive"))
      (node (ref "U1") (pin "102") (pinfunction "PA10_102") (pintype "bidirectional"))
    )
    (net (code "92") (name "/PA15") (class "Default")
      (node (ref "U1") (pin "110") (pinfunction "PA15(JTDI)_110") (pintype "bidirectional"))
    )
    (net (code "93") (name "/PB3") (class "Default")
      (node (ref "P1") (pin "2") (pinfunction "2_2") (pintype "passive"))
      (node (ref "U1") (pin "133") (pinfunction "PB3(JTDO/TRACESWO)_133") (pintype "bidirectional"))
    )
    (net (code "94") (name "/PB6") (class "Default")
      (node (ref "P8") (pin "1") (pinfunction "1_1") (pintype "passive"))
      (node (ref "R22") (pin "2") (pinfunction "2_2") (pintype "passive"))
      (node (ref "U1") (pin "136") (pinfunction "PB6_136") (pintype "bidirectional"))
    )
    (net (code "95") (name "/PB7") (class "Default")
      (node (ref "P8") (pin "2") (pinfunction "2_2") (pintype "passive"))
      (node (ref "R23") (pin "2") (pinfunction "2_2") (pintype "passive"))
      (node (ref "U1") (pin "137") (pinfunction "PB7_137") (pintype "bidirectional"))
    )
    (net (code "96") (name "/PB12") (class "Default")
      (node (ref "R18") (pin "1") (pinfunction "1_1") (pintype "passive"))
      (node (ref "U1") (pin "73") (pinfunction "PB12_73") (pintype "bidirectional"))
    )
    (net (code "97") (name "/PB13") (class "Default")
      (node (ref "R20") (pin "1") (pinfunction "1_1") (pintype "passive"))
      (node (ref "U1") (pin "74") (pinfunction "PB13_74") (pintype "bidirectional"))
    )
    (net (code "98") (name "/PB14") (class "Default")
      (node (ref "R21") (pin "1") (pinfunction "1_1") (pintype "passive"))
      (node (ref "U1") (pin "75") (pinfunction "PB14_75") (pintype "bidirectional"))
    )
    (net (code "99") (name "/PB15") (class "Default")
      (node (ref "R19") (pin "1") (pinfunction "1_1") (pintype "passive"))
      (node (ref "U1") (pin "76") (pinfunction "PB15_76") (pintype "bidirectional"))
    )
    (net (code "100") (name "/PC1") (class "Default")
      (node (ref "U1") (pin "27") (pinfunction "PC1_27") (pintype "bidirectional"))
    )
    (net (code "101") (name "/PC4") (class "Default")
      (node (ref "U1") (pin "44") (pinfunction "PC4_44") (pintype "bidirectional"))
    )
    (net (code "102") (name "/PC5") (class "Default")
      (node (ref "U1") (pin "45") (pinfunction "PC5_45") (pintype "bidirectional"))
    )
    (net (code "103") (name "/PC8") (class "Default")
      (node (ref "R12") (pin "1") (pinfunction "1_1") (pintype "passive"))
      (node (ref "U1") (pin "98") (pinfunction "PC8_98") (pintype "bidirectional"))
    )
    (net (code "104") (name "/PC9") (class "Default")
      (node (ref "R13") (pin "1") (pinfunction "1_1") (pintype "passive"))
      (node (ref "U1") (pin "99") (pinfunction "PC9_99") (pintype "bidirectional"))
    )
    (net (code "105") (name "/PC11") (class "Default")
      (node (ref "R15") (pin "1") (pinfunction "1_1") (pintype "passive"))
      (node (ref "U1") (pin "112") (pinfunction "PC11_112") (pintype "bidirectional"))
    )
    (net (code "106") (name "/PC12") (class "Default")
      (node (ref "R17") (pin "1") (pinfunction "1_1") (pintype "passive"))
      (node (ref "U1") (pin "113") (pinfunction "PC12_113") (pintype "bidirectional"))
    )
    (net (code "107") (name "/PC14") (class "Default")
      (node (ref "U1") (pin "8") (pinfunction "PC14-OSC32_IN(PC14)_8") (pintype "bidirectional"))
    )
    (net (code "108") (name "/PC15") (class "Default")
      (node (ref "U1") (pin "9") (pinfunction "PC15-OSC32_OUT(PC15)_9") (pintype "bidirectional"))
    )
    (net (code "109") (name "/PD2") (class "Default")
      (node (ref "R16") (pin "1") (pinfunction "1_1") (pintype "passive"))
      (node (ref "U1") (pin "116") (pinfunction "PD2_116") (pintype "bidirectional"))
    )
    (net (code "110") (name "/PD4") (class "Default")
      (node (ref "U1") (pin "118") (pinfunction "PD4_118") (pintype "bidirectional"))
    )
    (net (code "111") (name "/PD5") (class "Default")
      (node (ref "U1") (pin "119") (pinfunction "PD5_119") (pintype "bidirectional"))
    )
    (net (code "112") (name "/PD11") (class "Default")
      (node (ref "U1") (pin "80") (pinfunction "PD11_80") (pintype "bidirectional"))
    )
    (net (code "113") (name "/PE2") (class "Default")
      (node (ref "P4") (pin "2") (pinfunction "2_2") (pintype "passive"))
      (node (ref "U1") (pin "1") (pinfunction "PE2_1") (pintype "bidirectional"))
    )
    (net (code "114") (name "/PE3") (class "Default")
      (node (ref "U1") (pin "2") (pinfunction "PE3_2") (pintype "bidirectional"))
    )
    (net (code "115") (name "/PE4") (class "Default")
      (node (ref "P4") (pin "3") (pinfunction "3_3") (pintype "passive"))
      (node (ref "U1") (pin "3") (pinfunction "PE4_3") (pintype "bidirectional"))
    )
    (net (code "116") (name "/PE5") (class "Default")
      (node (ref "P9") (pin "2") (pinfunction "2_2") (pintype "passive"))
      (node (ref "U1") (pin "4") (pinfunction "PE5_4") (pintype "bidirectional"))
    )
    (net (code "117") (name "/PE6") (class "Default")
      (node (ref "U1") (pin "5") (pinfunction "PE6_5") (pintype "bidirectional"))
    )
    (net (code "118") (name "/PF6") (class "Default")
      (node (ref "P5") (pin "3") (pinfunction "3_3") (pintype "passive"))
      (node (ref "U1") (pin "18") (pinfunction "PF6_18") (pintype "bidirectional"))
    )
    (net (code "119") (name "/PF7") (class "Default")
      (node (ref "P5") (pin "2") (pinfunction "2_2") (pintype "passive"))
      (node (ref "U1") (pin "19") (pinfunction "PF7_19") (pintype "bidirectional"))
    )
    (net (code "120") (name "/PF8") (class "Default")
      (node (ref "P5") (pin "4") (pinfunction "4_4") (pintype "passive"))
      (node (ref "U1") (pin "20") (pinfunction "PF8_20") (pintype "bidirectional"))
    )
    (net (code "121") (name "/PF9") (class "Default")
      (node (ref "U1") (pin "21") (pinfunction "PF9_21") (pintype "bidirectional"))
    )
    (net (code "122") (name "/PG2") (class "Default")
      (node (ref "U1") (pin "87") (pinfunction "PG2_87") (pintype "bidirectional"))
    )
    (net (code "123") (name "/PH0") (class "Default")
      (node (ref "U1") (pin "23") (pinfunction "PH0-OSC_IN(PH0)_23") (pintype "bidirectional+no_connect"))
    )
    (net (code "124") (name "/PH1") (class "Default")
      (node (ref "U1") (pin "24") (pinfunction "PH1-OSC_OUT(PH1)_24") (pintype "bidirectional+no_connect"))
    )
    (net (code "125") (name "/SD_CLK") (class "Default")
      (node (ref "P3") (pin "5") (pinfunction "CLK_5") (pintype "passive"))
      (node (ref "R17") (pin "2") (pinfunction "2_2") (pintype "passive"))
      (node (ref "R20") (pin "2") (pinfunction "2_2") (pintype "passive"))
      (node (ref "R9") (pin "2") (pinfunction "2_2") (pintype "passive"))
    )
    (net (code "126") (name "/SD_CS{slash}DAT3") (class "Default")
      (node (ref "P3") (pin "2") (pinfunction "CS/DAT3_2") (pintype "passive"))
      (node (ref "R15") (pin "2") (pinfunction "2_2") (pintype "passive"))
      (node (ref "R18") (pin "2") (pinfunction "2_2") (pintype "passive"))
      (node (ref "R7") (pin "2") (pinfunction "2_2") (pintype "passive"))
    )
    (net (code "127") (name "/SD_DAT1") (class "Default")
      (node (ref "P3") (pin "8") (pinfunction "DAT1_8") (pintype "passive"))
      (node (ref "R11") (pin "2") (pinfunction "2_2") (pintype "passive"))
      (node (ref "R13") (pin "2") (pinfunction "2_2") (pintype "passive"))
    )
    (net (code "128") (name "/SD_DAT2") (class "Default")
      (node (ref "P3") (pin "1") (pinfunction "DAT2_1") (pintype "passive"))
      (node (ref "R14") (pin "2") (pinfunction "2_2") (pintype "passive"))
      (node (ref "R6") (pin "2") (pinfunction "2_2") (pintype "passive"))
    )
    (net (code "129") (name "/SD_DI{slash}CMD") (class "Default")
      (node (ref "P3") (pin "3") (pinfunction "DI/CMD_3") (pintype "passive"))
      (node (ref "R16") (pin "2") (pinfunction "2_2") (pintype "passive"))
      (node (ref "R19") (pin "2") (pinfunction "2_2") (pintype "passive"))
      (node (ref "R8") (pin "2") (pinfunction "2_2") (pintype "passive"))
    )
    (net (code "130") (name "/SD_DO{slash}DAT0") (class "Default")
      (node (ref "P3") (pin "7") (pinfunction "DO/DAT0_7") (pintype "passive"))
      (node (ref "R10") (pin "2") (pinfunction "2_2") (pintype "passive"))
      (node (ref "R12") (pin "2") (pinfunction "2_2") (pintype "passive"))
      (node (ref "R21") (pin "2") (pinfunction "2_2") (pintype "passive"))
    )
    (net (code "131") (name "/SWCLK") (class "Default")
      (node (ref "P1") (pin "4") (pinfunction "4_4") (pintype "passive"))
      (node (ref "U1") (pin "109") (pinfunction "PA14(JTCK-SWCLK)_109") (pintype "bidirectional"))
    )
    (net (code "132") (name "/SWDIO") (class "Default")
      (node (ref "P1") (pin "5") (pinfunction "5_5") (pintype "passive"))
      (node (ref "U1") (pin "105") (pinfunction "PA13(JTMS-SWDIO)_105") (pintype "bidirectional"))
    )
    (net (code "133") (name "3V3") (class "Default")
      (node (ref "C15") (pin "1") (pinfunction "1_1") (pintype "passive"))
      (node (ref "C16") (pin "1") (pinfunction "1_1") (pintype "passive"))
      (node (ref "C17") (pin "1") (pinfunction "1_1") (pintype "passive"))
      (node (ref "C18") (pin "1") (pinfunction "1_1") (pintype "passive"))
      (node (ref "C19") (pin "1") (pinfunction "1_1") (pintype "passive"))
      (node (ref "C2") (pin "2") (pinfunction "2_2") (pintype "passive"))
      (node (ref "C20") (pin "1") (pinfunction "1_1") (pintype "passive"))
      (node (ref "C21") (pin "1") (pinfunction "1_1") (pintype "passive"))
      (node (ref "C22") (pin "1") (pinfunction "1_1") (pintype "passive"))
      (node (ref "C23") (pin "1") (pinfunction "1_1") (pintype "passive"))
      (node (ref "C24") (pin "1") (pinfunction "1_1") (pintype "passive"))
      (node (ref "C25") (pin "1") (pinfunction "1_1") (pintype "passive"))
      (node (ref "C26") (pin "1") (pinfunction "1_1") (pintype "passive"))
      (node (ref "C27") (pin "1") (pinfunction "1_1") (pintype "passive"))
      (node (ref "C28") (pin "1") (pinfunction "1_1") (pintype "passive"))
      (node (ref "C3") (pin "2") (pinfunction "2_2") (pintype "passive"))
      (node (ref "C4") (pin "2") (pinfunction "2_2") (pintype "passive"))
      (node (ref "C5") (pin "2") (pinfunction "2_2") (pintype "passive"))
      (node (ref "C6") (pin "2") (pinfunction "2_2") (pintype "passive"))
      (node (ref "C7") (pin "2") (pinfunction "2_2") (pintype "passive"))
      (node (ref "C8") (pin "1") (pinfunction "1_1") (pintype "passive"))
      (node (ref "C9") (pin "1") (pinfunction "1_1") (pintype "passive"))
      (node (ref "M1") (pin "5") (pinfunction "3V3_5") (pintype "passive"))
      (node (ref "P2") (pin "1") (pinfunction "1_1") (pintype "passive"))
      (node (ref "P3") (pin "4") (pinfunction "VCC_4") (pintype "passive"))
      (node (ref "P4") (pin "1") (pinfunction "1_1") (pintype "passive"))
      (node (ref "P5") (pin "1") (pinfunction "1_1") (pintype "passive"))
      (node (ref "R10") (pin "1") (pinfunction "1_1") (pintype "passive"))
      (node (ref "R11") (pin "1") (pinfunction "1_1") (pintype "passive"))
      (node (ref "R2") (pin "2") (pinfunction "2_2") (pintype "passive"))
      (node (ref "R22") (pin "1") (pinfunction "1_1") (pintype "passive"))
      (node (ref "R23") (pin "1") (pinfunction "1_1") (pintype "passive"))
      (node (ref "R24") (pin "1") (pinfunction "1_1") (pintype "passive"))
      (node (ref "R25") (pin "1") (pinfunction "1_1") (pintype "passive"))
      (node (ref "R5") (pin "1") (pinfunction "1_1") (pintype "passive"))
      (node (ref "R6") (pin "1") (pinfunction "1_1") (pintype "passive"))
      (node (ref "R7") (pin "1") (pinfunction "1_1") (pintype "passive"))
      (node (ref "R8") (pin "1") (pinfunction "1_1") (pintype "passive"))
      (node (ref "R9") (pin "1") (pinfunction "1_1") (pintype "passive"))
      (node (ref "SW2") (pin "3") (pinfunction "B2_3") (pintype "passive"))
      (node (ref "SW2") (pin "4") (pinfunction "B1_4") (pintype "passive"))
      (node (ref "U1") (pin "108") (pinfunction "VDD_108") (pintype "power_in"))
      (node (ref "U1") (pin "121") (pinfunction "VDD_121") (pintype "power_in"))
      (node (ref "U1") (pin "131") (pinfunction "VDD_131") (pintype "power_in"))
      (node (ref "U1") (pin "143") (pinfunction "PDR_ON_143") (pintype "input"))
      (node (ref "U1") (pin "144") (pinfunction "VDD_144") (pintype "power_in"))
      (node (ref "U1") (pin "17") (pinfunction "VDD_17") (pintype "power_in"))
      (node (ref "U1") (pin "30") (pinfunction "VDD_30") (pintype "power_in"))
      (node (ref "U1") (pin "33") (pinfunction "VDDA_33") (pintype "power_in"))
      (node (ref "U1") (pin "39") (pinfunction "VDD_39") (pintype "power_in"))
      (node (ref "U1") (pin "52") (pinfunction "VDD_52") (pintype "power_in"))
      (node (ref "U1") (pin "62") (pinfunction "VDD_62") (pintype "power_in"))
      (node (ref "U1") (pin "72") (pinfunction "VDD_72") (pintype "power_in"))
      (node (ref "U1") (pin "84") (pinfunction "VDD_84") (pintype "power_in"))
      (node (ref "U1") (pin "95") (pinfunction "VDD_95") (pintype "power_in"))
      (node (ref "U2") (pin "1") (pinfunction "VDD_1") (pintype "passive"))
      (node (ref "U2") (pin "14") (pinfunction "VDD_14") (pintype "passive"))
      (node (ref "U2") (pin "27") (pinfunction "VDD_27") (pintype "passive"))
      (node (ref "U2") (pin "3") (pinfunction "VDDQ_3") (pintype "passive"))
      (node (ref "U2") (pin "43") (pinfunction "VDDQ_43") (pintype "passive"))
      (node (ref "U2") (pin "49") (pinfunction "VDDQ_49") (pintype "passive"))
      (node (ref "U2") (pin "9") (pinfunction "VDDQ_9") (pintype "passive"))
    )
    (net (code "134") (name "5V") (class "Default")
      (node (ref "M1") (pin "7") (pinfunction "5V_7") (pintype "passive"))
      (node (ref "P2") (pin "3") (pinfunction "3_3") (pintype "passive"))
    )
    (net (code "135") (name "GND") (class "Default")
      (node (ref "C1") (pin "1") (pinfunction "1_1") (pintype "passive"))
      (node (ref "C10") (pin "1") (pinfunction "1_1") (pintype "passive"))
      (node (ref "C11") (pin "1") (pinfunction "1_1") (pintype "passive"))
      (node (ref "C12") (pin "2") (pinfunction "2_2") (pintype "passive"))
      (node (ref "C13") (pin "2") (pinfunction "2_2") (pintype "passive"))
      (node (ref "C14") (pin "2") (pinfunction "2_2") (pintype "passive"))
      (node (ref "C15") (pin "2") (pinfunction "2_2") (pintype "passive"))
      (node (ref "C16") (pin "2") (pinfunction "2_2") (pintype "passive"))
      (node (ref "C17") (pin "2") (pinfunction "2_2") (pintype "passive"))
      (node (ref "C18") (pin "2") (pinfunction "2_2") (pintype "passive"))
      (node (ref "C19") (pin "2") (pinfunction "2_2") (pintype "passive"))
      (node (ref "C2") (pin "1") (pinfunction "1_1") (pintype "passive"))
      (node (ref "C20") (pin "2") (pinfunction "2_2") (pintype "passive"))
      (node (ref "C21") (pin "2") (pinfunction "2_2") (pintype "passive"))
      (node (ref "C22") (pin "2") (pinfunction "2_2") (pintype "passive"))
      (node (ref "C23") (pin "2") (pinfunction "2_2") (pintype "passive"))
      (node (ref "C24") (pin "2") (pinfunction "2_2") (pintype "passive"))
      (node (ref "C25") (pin "2") (pinfunction "2_2") (pintype "passive"))
      (node (ref "C26") (pin "2") (pinfunction "2_2") (pintype "passive"))
      (node (ref "C27") (pin "2") (pinfunction "2_2") (pintype "passive"))
      (node (ref "C28") (pin "2") (pinfunction "2_2") (pintype "passive"))
      (node (ref "C3") (pin "1") (pinfunction "1_1") (pintype "passive"))
      (node (ref "C4") (pin "1") (pinfunction "1_1") (pintype "passive"))
      (node (ref "C5") (pin "1") (pinfunction "1_1") (pintype "passive"))
      (node (ref "C6") (pin "1") (pinfunction "1_1") (pintype "passive"))
      (node (ref "C7") (pin "1") (pinfunction "1_1") (pintype "passive"))
      (node (ref "C8") (pin "2") (pinfunction "2_2") (pintype "passive"))
      (node (ref "C9") (pin "2") (pinfunction "2_2") (pintype "passive"))
      (node (ref "D1") (pin "2") (pinfunction "-_2") (pintype "passive"))
      (node (ref "M1") (pin "6") (pinfunction "GND_6") (pintype "passive"))
      (node (ref "M1") (pin "8") (pinfunction "GND_8") (pintype "passive"))
      (node (ref "P1") (pin "3") (pinfunction "3_3") (pintype "passive"))
      (node (ref "P3") (pin "6") (pinfunction "GND_6") (pintype "passive"))
      (node (ref "P3") (pin "9") (pinfunction "NC_9") (pintype "passive"))
      (node (ref "P4") (pin "5") (pinfunction "5_5") (pintype "passive"))
      (node (ref "P5") (pin "5") (pinfunction "5_5") (pintype "passive"))
      (node (ref "P6") (pin "5") (pinfunction "GND_5") (pintype "passive"))
      (node (ref "P7") (pin "2") (pinfunction "2_2") (pintype "passive"))
      (node (ref "P8") (pin "3") (pinfunction "3_3") (pintype "passive"))
      (node (ref "P8") (pin "6") (pinfunction "6_6") (pintype "passive"))
      (node (ref "R3") (pin "1") (pinfunction "1_1") (pintype "passive"))
      (node (ref "R4") (pin "1") (pinfunction "1_1") (pintype "passive"))
      (node (ref "SW1") (pin "3") (pinfunction "3_3") (pintype "passive"))
      (node (ref "SW1") (pin "4") (pinfunction "4_4") (pintype "passive"))
      (node (ref "U1") (pin "107") (pinfunction "VSS_107") (pintype "power_in"))
      (node (ref "U1") (pin "120") (pinfunction "VSS_120") (pintype "power_in"))
      (node (ref "U1") (pin "130") (pinfunction "VSS_130") (pintype "power_in"))
      (node (ref "U1") (pin "16") (pinfunction "VSS_16") (pintype "power_in"))
      (node (ref "U1") (pin "31") (pinfunction "VSSA_31") (pintype "power_in"))
      (node (ref "U1") (pin "38") (pinfunction "VSS_38") (pintype "power_in"))
      (node (ref "U1") (pin "51") (pinfunction "VSS_51") (pintype "power_in"))
      (node (ref "U1") (pin "61") (pinfunction "VSS_61") (pintype "power_in"))
      (node (ref "U1") (pin "83") (pinfunction "VSS_83") (pintype "power_in"))
      (node (ref "U1") (pin "94") (pinfunction "VSS_94") (pintype "power_in"))
      (node (ref "U2") (pin "12") (pinfunction "GNDQ_12") (pintype "passive"))
      (node (ref "U2") (pin "28") (pinfunction "GND_28") (pintype "passive"))
      (node (ref "U2") (pin "41") (pinfunction "GND_41") (pintype "passive"))
      (node (ref "U2") (pin "46") (pinfunction "GNDQ_46") (pintype "passive"))
      (node (ref "U2") (pin "52") (pinfunction "GNDQ_52") (pintype "passive"))
      (node (ref "U2") (pin "54") (pinfunction "GND_54") (pintype "passive"))
      (node (ref "U2") (pin "6") (pinfunction "GNDQ_6") (pintype "passive"))
    )
    (net (code "136") (name "Net-(D1-+)") (class "Default")
      (node (ref "D1") (pin "1") (pinfunction "+_1") (pintype "passive"))
      (node (ref "R24") (pin "2") (pinfunction "2_2") (pintype "passive"))
    )
    (net (code "137") (name "Net-(D2-+)") (class "Default")
      (node (ref "D2") (pin "1") (pinfunction "+_1") (pintype "passive"))
      (node (ref "R25") (pin "2") (pinfunction "2_2") (pintype "passive"))
    )
    (net (code "138") (name "Net-(M1-VBAT)") (class "Default")
      (node (ref "M1") (pin "2") (pinfunction "VBAT_2") (pintype "passive"))
      (node (ref "P7") (pin "1") (pinfunction "1_1") (pintype "passive"))
    )
    (net (code "139") (name "Net-(M1-VDD)") (class "Default")
      (node (ref "M1") (pin "1") (pinfunction "VDD_1") (pintype "passive"))
      (node (ref "P6") (pin "1") (pinfunction "VCC_1") (pintype "passive"))
    )
    (net (code "140") (name "Net-(P1-Pad1)") (class "Default")
      (node (ref "P1") (pin "1") (pinfunction "1_1") (pintype "passive"))
      (node (ref "P2") (pin "2") (pinfunction "2_2") (pintype "passive"))
    )
    (net (code "141") (name "Net-(P4-Pad4)") (class "Default")
      (node (ref "P4") (pin "4") (pinfunction "4_4") (pintype "passive"))
      (node (ref "P9") (pin "3") (pinfunction "3_3") (pintype "passive"))
    )
    (net (code "142") (name "Net-(U1B-VCAP_1)") (class "Default")
      (node (ref "C14") (pin "1") (pinfunction "1_1") (pintype "passive"))
      (node (ref "U1") (pin "71") (pinfunction "VCAP_1_71") (pintype "power_in"))
    )
    (net (code "143") (name "Net-(U1B-VCAP_2)") (class "Default")
      (node (ref "C13") (pin "1") (pinfunction "1_1") (pintype "passive"))
      (node (ref "U1") (pin "106") (pinfunction "VCAP_2_106") (pintype "power_in"))
    )
    (net (code "144") (name "Net-(U1C-VBAT)") (class "Default")
      (node (ref "C12") (pin "1") (pinfunction "1_1") (pintype "passive"))
      (node (ref "R2") (pin "1") (pinfunction "1_1") (pintype "passive"))
      (node (ref "U1") (pin "6") (pinfunction "VBAT_6") (pintype "power_in"))
    )
    (net (code "145") (name "Net-(U1C-VREF+)") (class "Default")
      (node (ref "C10") (pin "2") (pinfunction "2_2") (pintype "passive"))
      (node (ref "C11") (pin "2") (pinfunction "2_2") (pintype "passive"))
      (node (ref "R5") (pin "2") (pinfunction "2_2") (pintype "passive"))
      (node (ref "U1") (pin "32") (pinfunction "VREF+_32") (pintype "power_in"))
    )
    (net (code "146") (name "unconnected-(P6-D+-Pad3)") (class "Default")
      (node (ref "P6") (pin "3") (pinfunction "D+_3") (pintype "passive"))
    )
    (net (code "147") (name "unconnected-(P6-D--Pad2)") (class "Default")
      (node (ref "P6") (pin "2") (pinfunction "D-_2") (pintype "passive"))
    )
    (net (code "148") (name "unconnected-(P6-ID-Pad4)") (class "Default")
      (node (ref "P6") (pin "4") (pinfunction "ID_4") (pintype "passive"))
    )
    (net (code "149") (name "unconnected-(U2-NC-Pad36)") (class "Default")
      (node (ref "U2") (pin "36") (pinfunction "NC_36") (pintype "passive+no_connect"))
    )
    (net (code "150") (name "unconnected-(U2-NC-Pad40)") (class "Default")
      (node (ref "U2") (pin "40") (pinfunction "NC_40") (pintype "passive+no_connect"))
    )
  )
)
